# MicroSDBreakout-V1.net
KiCad netlist of a schematic drawn in EAGLE
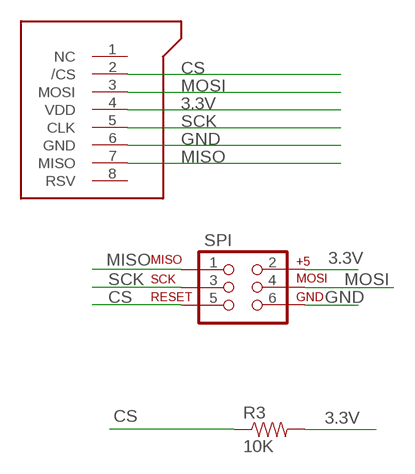
[diagram p0: schematic, sheet 1]

(export (version "E")
  (design (tool "Eeschema 10.0.6"))
  (components
    (comp (ref "R3")
      (value "10K")
      (footprint "eagle-import:0603-RES")
      (libsource (lib "eagle-import") (part "RESISTOR0603-RES"))
    )
    (comp (ref "SPI")
      (value "AVR_SPI_PRG_6PTH")
      (footprint "eagle-import:2X3")
      (libsource (lib "eagle-import") (part "AVR_SPI_PRG_6PTH"))
    )
    (comp (ref "U$1")
      (value "MICROSD")
      (footprint "eagle-import:MICRO-SD-SOCKET-PP")
      (libsource (lib "eagle-import") (part "MICROSD"))
    )
  )
  (nets
    (net (code "1") (name "/3.3V") (class "Default")
      (node (ref "R3") (pin "2") (pinfunction "2_2") (pintype "passive"))
      (node (ref "SPI") (pin "2") (pinfunction "2_2") (pintype "passive"))
      (node (ref "U$1") (pin "4") (pinfunction "VDD_4") (pintype "bidirectional"))
    )
    (net (code "2") (name "/CS") (class "Default")
      (node (ref "R3") (pin "1") (pinfunction "1_1") (pintype "passive"))
      (node (ref "SPI") (pin "5") (pinfunction "5_5") (pintype "passive"))
      (node (ref "U$1") (pin "2") (pinfunction "/CS_2") (pintype "bidirectional"))
    )
    (net (code "3") (name "/GND") (class "Default")
      (node (ref "SPI") (pin "6") (pinfunction "6_6") (pintype "passive"))
      (node (ref "U$1") (pin "6") (pinfunction "GND_6") (pintype "bidirectional"))
    )
    (net (code "4") (name "/MISO") (class "Default")
      (node (ref "SPI") (pin "1") (pinfunction "1_1") (pintype "passive"))
      (node (ref "U$1") (pin "7") (pinfunction "MISO_7") (pintype "bidirectional"))
    )
    (net (code "5") (name "/MOSI") (class "Default")
      (node (ref "SPI") (pin "4") (pinfunction "4_4") (pintype "passive"))
      (node (ref "U$1") (pin "3") (pinfunction "MOSI_3") (pintype "bidirectional"))
    )
    (net (code "6") (name "/SCK") (class "Default")
      (node (ref "SPI") (pin "3") (pinfunction "3_3") (pintype "passive"))
      (node (ref "U$1") (pin "5") (pinfunction "CLK_5") (pintype "bidirectional"))
    )
    (net (code "7") (name "unconnected-(U$1-NC-Pad1)") (class "Default")
      (node (ref "U$1") (pin "1") (pinfunction "NC_1") (pintype "bidirectional"))
    )
    (net (code "8") (name "unconnected-(U$1-RSV-Pad8)") (class "Default")
      (node (ref "U$1") (pin "8") (pinfunction "RSV_8") (pintype "bidirectional"))
    )
  )
)
